# FPGA.net
KiCad netlist of a schematic drawn in Altium Designer
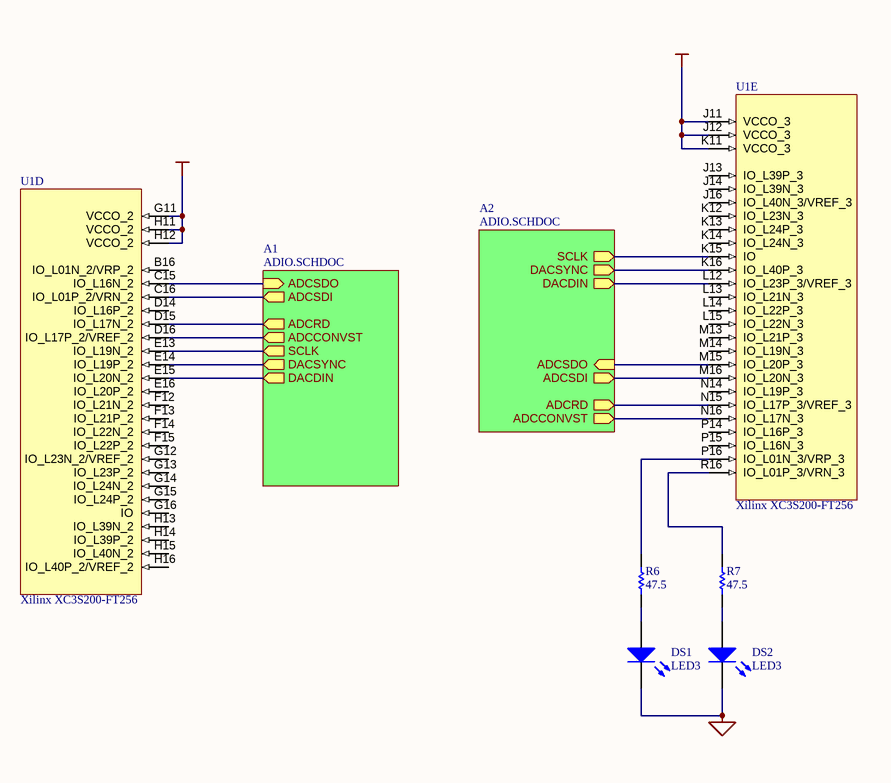
[diagram p0: FPGA.SCHDOC]

(export (version "E")
  (design (tool "Eeschema 10.0.6"))
  (components
    (comp (ref "DS1")
      (value "LED3")
      (footprint "SMD _LED")
      (description "Typical BLUE SiC LED")
      (fields (field (name "PUBLISHER") "Altium Limited"))
      (libsource (lib "Miscellaneous Devices") (part "LED3"))
    )
    (comp (ref "DS2")
      (value "LED3")
      (footprint "SMD _LED")
      (description "Typical BLUE SiC LED")
      (fields (field (name "PUBLISHER") "Altium Limited"))
      (libsource (lib "Miscellaneous Devices") (part "LED3"))
    )
    (comp (ref "R6")
      (value "47.5")
      (footprint "0603")
      (description "Standard Passive Resistor")
      (fields (field (name "TOLERANCE") "1%") (field (name "Comment") "current-limiting series res"))
      (libsource (lib "parts") (part "RESISTOR"))
    )
    (comp (ref "R7")
      (value "47.5")
      (footprint "0603")
      (description "Standard Passive Resistor")
      (fields (field (name "TOLERANCE") "1%") (field (name "Comment") "current-limiting series res"))
      (libsource (lib "parts") (part "RESISTOR"))
    )
    (comp (ref "U1")
      (value "Xilinx XC3S200-FT256")
      (footprint "Xilinx FT256 BGA")
      (description "Xilinx Spartan-3 FPGA")
      (libsource (lib "") (part "XC3S200-FT256_1"))
    )
  )
  (nets
    (net (code "1") (name "/ADCCONVST") (class "Default")
      (node (ref "U1") (pin "N16") (pinfunction "IO_L17N_3_N16") (pintype "input"))
    )
    (net (code "2") (name "/ADCCONVST_1") (class "Default")
      (node (ref "U1") (pin "D16") (pinfunction "IO_L17P_2/VREF_2_D16") (pintype "input"))
    )
    (net (code "3") (name "/ADCRD") (class "Default")
      (node (ref "U1") (pin "N15") (pinfunction "IO_L17P_3/VREF_3_N15") (pintype "input"))
    )
    (net (code "4") (name "/ADCRD_1") (class "Default")
      (node (ref "U1") (pin "D15") (pinfunction "IO_L17N_2_D15") (pintype "input"))
    )
    (net (code "5") (name "/ADCSDI") (class "Default")
      (node (ref "U1") (pin "M16") (pinfunction "IO_L20N_3_M16") (pintype "input"))
    )
    (net (code "6") (name "/ADCSDI_1") (class "Default")
      (node (ref "U1") (pin "C16") (pinfunction "IO_L01P_2/VRN_2_C16") (pintype "input"))
    )
    (net (code "7") (name "/ADCSDO") (class "Default")
      (node (ref "U1") (pin "M15") (pinfunction "IO_L20P_3_M15") (pintype "input"))
    )
    (net (code "8") (name "/ADCSDO_1") (class "Default")
      (node (ref "U1") (pin "C15") (pinfunction "IO_L16N_2_C15") (pintype "input"))
    )
    (net (code "9") (name "/DACDIN") (class "Default")
      (node (ref "U1") (pin "L12") (pinfunction "IO_L23P_3/VREF_3_L12") (pintype "input"))
    )
    (net (code "10") (name "/DACDIN_1") (class "Default")
      (node (ref "U1") (pin "E15") (pinfunction "IO_L20N_2_E15") (pintype "input"))
    )
    (net (code "11") (name "/DACSYNC") (class "Default")
      (node (ref "U1") (pin "K16") (pinfunction "IO_L40P_3_K16") (pintype "input"))
    )
    (net (code "12") (name "/DACSYNC_1") (class "Default")
      (node (ref "U1") (pin "E14") (pinfunction "IO_L19P_2_E14") (pintype "input"))
    )
    (net (code "13") (name "/SCLK") (class "Default")
      (node (ref "U1") (pin "K15") (pinfunction "IO_K15") (pintype "input"))
    )
    (net (code "14") (name "/SCLK_1") (class "Default")
      (node (ref "U1") (pin "E13") (pinfunction "IO_L19N_2_E13") (pintype "input"))
    )
    (net (code "15") (name "GND") (class "Default")
      (node (ref "DS1") (pin "2") (pinfunction "K_2") (pintype "passive"))
      (node (ref "DS2") (pin "2") (pinfunction "K_2") (pintype "passive"))
    )
    (net (code "16") (name "Net-(DS1-A)") (class "Default")
      (node (ref "DS1") (pin "1") (pinfunction "A_1") (pintype "passive"))
      (node (ref "R6") (pin "2") (pintype "passive"))
    )
    (net (code "17") (name "Net-(DS2-A)") (class "Default")
      (node (ref "DS2") (pin "1") (pinfunction "A_1") (pintype "passive"))
      (node (ref "R7") (pin "2") (pintype "passive"))
    )
    (net (code "18") (name "Net-(U1E-IO_L01N_3{slash}VRP_3)") (class "Default")
      (node (ref "R6") (pin "1") (pintype "passive"))
      (node (ref "U1") (pin "P16") (pinfunction "IO_L01N_3/VRP_3_P16") (pintype "input"))
    )
    (net (code "19") (name "Net-(U1E-IO_L01P_3{slash}VRN_3)") (class "Default")
      (node (ref "R7") (pin "1") (pintype "passive"))
      (node (ref "U1") (pin "R16") (pinfunction "IO_L01P_3/VRN_3_R16") (pintype "input"))
    )
    (net (code "20") (name "VCC") (class "Default")
      (node (ref "U1") (pin "G11") (pinfunction "VCCO_2_G11") (pintype "input"))
      (node (ref "U1") (pin "H11") (pinfunction "VCCO_2_H11") (pintype "input"))
      (node (ref "U1") (pin "H12") (pinfunction "VCCO_2_H12") (pintype "input"))
      (node (ref "U1") (pin "J11") (pinfunction "VCCO_3_J11") (pintype "input"))
      (node (ref "U1") (pin "J12") (pinfunction "VCCO_3_J12") (pintype "input"))
      (node (ref "U1") (pin "K11") (pinfunction "VCCO_3_K11") (pintype "input"))
    )
    (net (code "21") (name "unconnected-(U1D-IO-PadG16)") (class "Default")
      (node (ref "U1") (pin "G16") (pinfunction "IO_G16") (pintype "input"))
    )
    (net (code "22") (name "unconnected-(U1D-IO_L01N_2{slash}VRP_2-PadB16)") (class "Default")
      (node (ref "U1") (pin "B16") (pinfunction "IO_L01N_2/VRP_2_B16") (pintype "input"))
    )
    (net (code "23") (name "unconnected-(U1D-IO_L16P_2-PadD14)") (class "Default")
      (node (ref "U1") (pin "D14") (pinfunction "IO_L16P_2_D14") (pintype "input"))
    )
    (net (code "24") (name "unconnected-(U1D-IO_L20P_2-PadE16)") (class "Default")
      (node (ref "U1") (pin "E16") (pinfunction "IO_L20P_2_E16") (pintype "input"))
    )
    (net (code "25") (name "unconnected-(U1D-IO_L21N_2-PadF12)") (class "Default")
      (node (ref "U1") (pin "F12") (pinfunction "IO_L21N_2_F12") (pintype "input"))
    )
    (net (code "26") (name "unconnected-(U1D-IO_L21P_2-PadF13)") (class "Default")
      (node (ref "U1") (pin "F13") (pinfunction "IO_L21P_2_F13") (pintype "input"))
    )
    (net (code "27") (name "unconnected-(U1D-IO_L22N_2-PadF14)") (class "Default")
      (node (ref "U1") (pin "F14") (pinfunction "IO_L22N_2_F14") (pintype "input"))
    )
    (net (code "28") (name "unconnected-(U1D-IO_L22P_2-PadF15)") (class "Default")
      (node (ref "U1") (pin "F15") (pinfunction "IO_L22P_2_F15") (pintype "input"))
    )
    (net (code "29") (name "unconnected-(U1D-IO_L23N_2{slash}VREF_2-PadG12)") (class "Default")
      (node (ref "U1") (pin "G12") (pinfunction "IO_L23N_2/VREF_2_G12") (pintype "input"))
    )
    (net (code "30") (name "unconnected-(U1D-IO_L23P_2-PadG13)") (class "Default")
      (node (ref "U1") (pin "G13") (pinfunction "IO_L23P_2_G13") (pintype "input"))
    )
    (net (code "31") (name "unconnected-(U1D-IO_L24N_2-PadG14)") (class "Default")
      (node (ref "U1") (pin "G14") (pinfunction "IO_L24N_2_G14") (pintype "input"))
    )
    (net (code "32") (name "unconnected-(U1D-IO_L24P_2-PadG15)") (class "Default")
      (node (ref "U1") (pin "G15") (pinfunction "IO_L24P_2_G15") (pintype "input"))
    )
    (net (code "33") (name "unconnected-(U1D-IO_L39N_2-PadH13)") (class "Default")
      (node (ref "U1") (pin "H13") (pinfunction "IO_L39N_2_H13") (pintype "input"))
    )
    (net (code "34") (name "unconnected-(U1D-IO_L39P_2-PadH14)") (class "Default")
      (node (ref "U1") (pin "H14") (pinfunction "IO_L39P_2_H14") (pintype "input"))
    )
    (net (code "35") (name "unconnected-(U1D-IO_L40N_2-PadH15)") (class "Default")
      (node (ref "U1") (pin "H15") (pinfunction "IO_L40N_2_H15") (pintype "input"))
    )
    (net (code "36") (name "unconnected-(U1D-IO_L40P_2{slash}VREF_2-PadH16)") (class "Default")
      (node (ref "U1") (pin "H16") (pinfunction "IO_L40P_2/VREF_2_H16") (pintype "input"))
    )
    (net (code "37") (name "unconnected-(U1E-IO_L16N_3-PadP15)") (class "Default")
      (node (ref "U1") (pin "P15") (pinfunction "IO_L16N_3_P15") (pintype "input"))
    )
    (net (code "38") (name "unconnected-(U1E-IO_L16P_3-PadP14)") (class "Default")
      (node (ref "U1") (pin "P14") (pinfunction "IO_L16P_3_P14") (pintype "input"))
    )
    (net (code "39") (name "unconnected-(U1E-IO_L19N_3-PadM14)") (class "Default")
      (node (ref "U1") (pin "M14") (pinfunction "IO_L19N_3_M14") (pintype "input"))
    )
    (net (code "40") (name "unconnected-(U1E-IO_L19P_3-PadN14)") (class "Default")
      (node (ref "U1") (pin "N14") (pinfunction "IO_L19P_3_N14") (pintype "input"))
    )
    (net (code "41") (name "unconnected-(U1E-IO_L21N_3-PadL13)") (class "Default")
      (node (ref "U1") (pin "L13") (pinfunction "IO_L21N_3_L13") (pintype "input"))
    )
    (net (code "42") (name "unconnected-(U1E-IO_L21P_3-PadM13)") (class "Default")
      (node (ref "U1") (pin "M13") (pinfunction "IO_L21P_3_M13") (pintype "input"))
    )
    (net (code "43") (name "unconnected-(U1E-IO_L22N_3-PadL15)") (class "Default")
      (node (ref "U1") (pin "L15") (pinfunction "IO_L22N_3_L15") (pintype "input"))
    )
    (net (code "44") (name "unconnected-(U1E-IO_L22P_3-PadL14)") (class "Default")
      (node (ref "U1") (pin "L14") (pinfunction "IO_L22P_3_L14") (pintype "input"))
    )
    (net (code "45") (name "unconnected-(U1E-IO_L23N_3-PadK12)") (class "Default")
      (node (ref "U1") (pin "K12") (pinfunction "IO_L23N_3_K12") (pintype "input"))
    )
    (net (code "46") (name "unconnected-(U1E-IO_L24N_3-PadK14)") (class "Default")
      (node (ref "U1") (pin "K14") (pinfunction "IO_L24N_3_K14") (pintype "input"))
    )
    (net (code "47") (name "unconnected-(U1E-IO_L24P_3-PadK13)") (class "Default")
      (node (ref "U1") (pin "K13") (pinfunction "IO_L24P_3_K13") (pintype "input"))
    )
    (net (code "48") (name "unconnected-(U1E-IO_L39N_3-PadJ14)") (class "Default")
      (node (ref "U1") (pin "J14") (pinfunction "IO_L39N_3_J14") (pintype "input"))
    )
    (net (code "49") (name "unconnected-(U1E-IO_L39P_3-PadJ13)") (class "Default")
      (node (ref "U1") (pin "J13") (pinfunction "IO_L39P_3_J13") (pintype "input"))
    )
    (net (code "50") (name "unconnected-(U1E-IO_L40N_3{slash}VREF_3-PadJ16)") (class "Default")
      (node (ref "U1") (pin "J16") (pinfunction "IO_L40N_3/VREF_3_J16") (pintype "input"))
    )
  )
)
